# BATT_BUTTONS.net
KiCad netlist of a schematic drawn in EAGLE
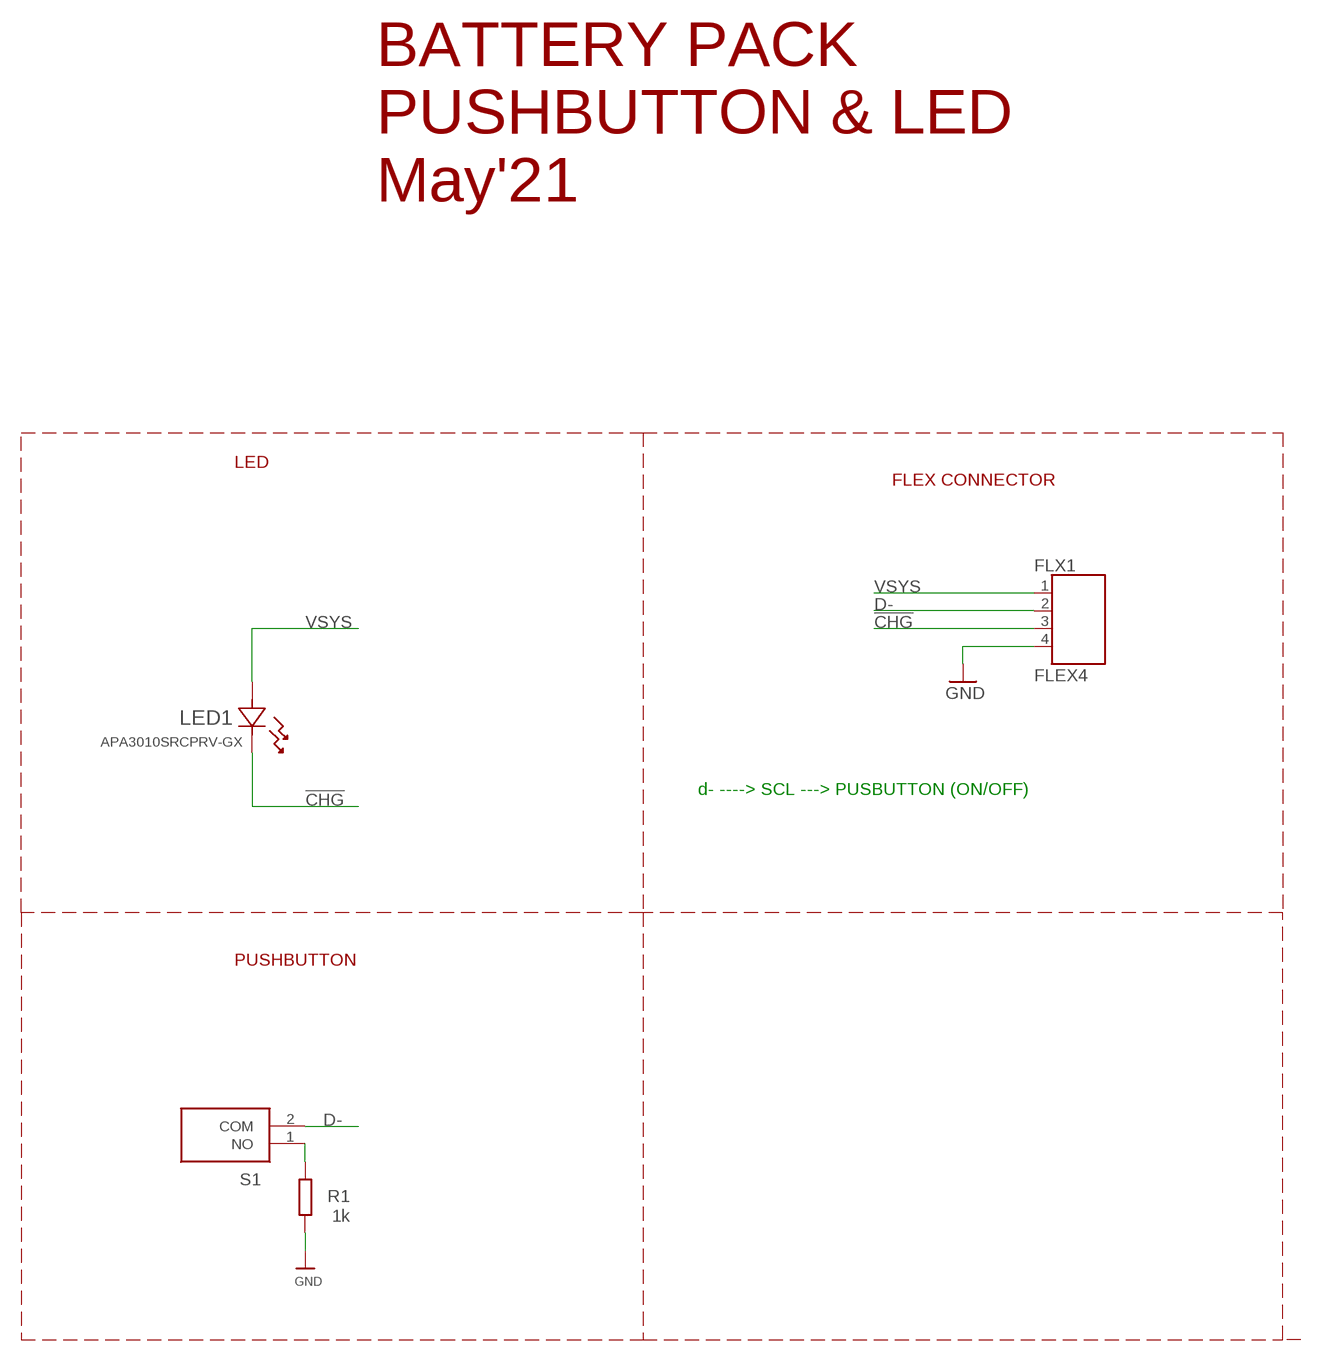
[diagram p0: schematic, sheet 1]

(export (version "E")
  (design (tool "Eeschema 10.0.6"))
  (components
    (comp (ref "FLX1")
      (value "FLEX4")
      (footprint "eagle-import:FLEX4")
      (libsource (lib "eagle-import") (part "FLEX4"))
    )
    (comp (ref "LED1")
      (value "APA3010SRCPRV-GX")
      (footprint "eagle-import:LED_APA3010SRCPRV-GX_KNB")
      (fields (field (name "COPYRIGHT") "Copyright (C) 2018 Accelerated Designs. All rights reserved"))
      (libsource (lib "eagle-import") (part "APA3010SRCPRV-GX"))
    )
    (comp (ref "R1")
      (value "1k")
      (footprint "eagle-import:R0603")
      (libsource (lib "eagle-import") (part "R-EU_R0603"))
    )
    (comp (ref "S1")
      (value "KXT311LHS")
      (footprint "eagle-import:KXT311LHS")
      (fields (field (name "MOUSER_PART_NUMBER") "611-KXT311LHS"))
      (libsource (lib "eagle-import") (part "KXT311LHS"))
    )
  )
  (nets
    (net (code "1") (name "/D-") (class "Default")
      (node (ref "FLX1") (pin "2") (pinfunction "2_2") (pintype "passive"))
      (node (ref "S1") (pin "2") (pinfunction "COM_2") (pintype "bidirectional"))
    )
    (net (code "2") (name "/VSYS") (class "Default")
      (node (ref "FLX1") (pin "1") (pinfunction "1_1") (pintype "passive"))
      (node (ref "LED1") (pin "2") (pinfunction "2_2") (pintype "passive"))
    )
    (net (code "3") (name "/~{CHG}") (class "Default")
      (node (ref "FLX1") (pin "3") (pinfunction "3_3") (pintype "passive"))
      (node (ref "LED1") (pin "1") (pinfunction "1_1") (pintype "passive"))
    )
    (net (code "4") (name "GND") (class "Default")
      (node (ref "FLX1") (pin "4") (pinfunction "4_4") (pintype "passive"))
      (node (ref "R1") (pin "1") (pinfunction "1_1") (pintype "passive"))
    )
    (net (code "5") (name "Net-(S1-NO)") (class "Default")
      (node (ref "R1") (pin "2") (pinfunction "2_2") (pintype "passive"))
      (node (ref "S1") (pin "1") (pinfunction "NO_1") (pintype "bidirectional"))
    )
  )
)
